# Spring2020V1_5.net
KiCad netlist of a schematic drawn in EAGLE
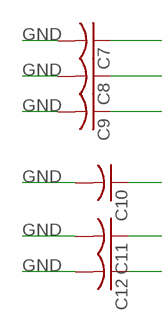
[diagram p0: schematic, sheet 1, part 1 of 2]
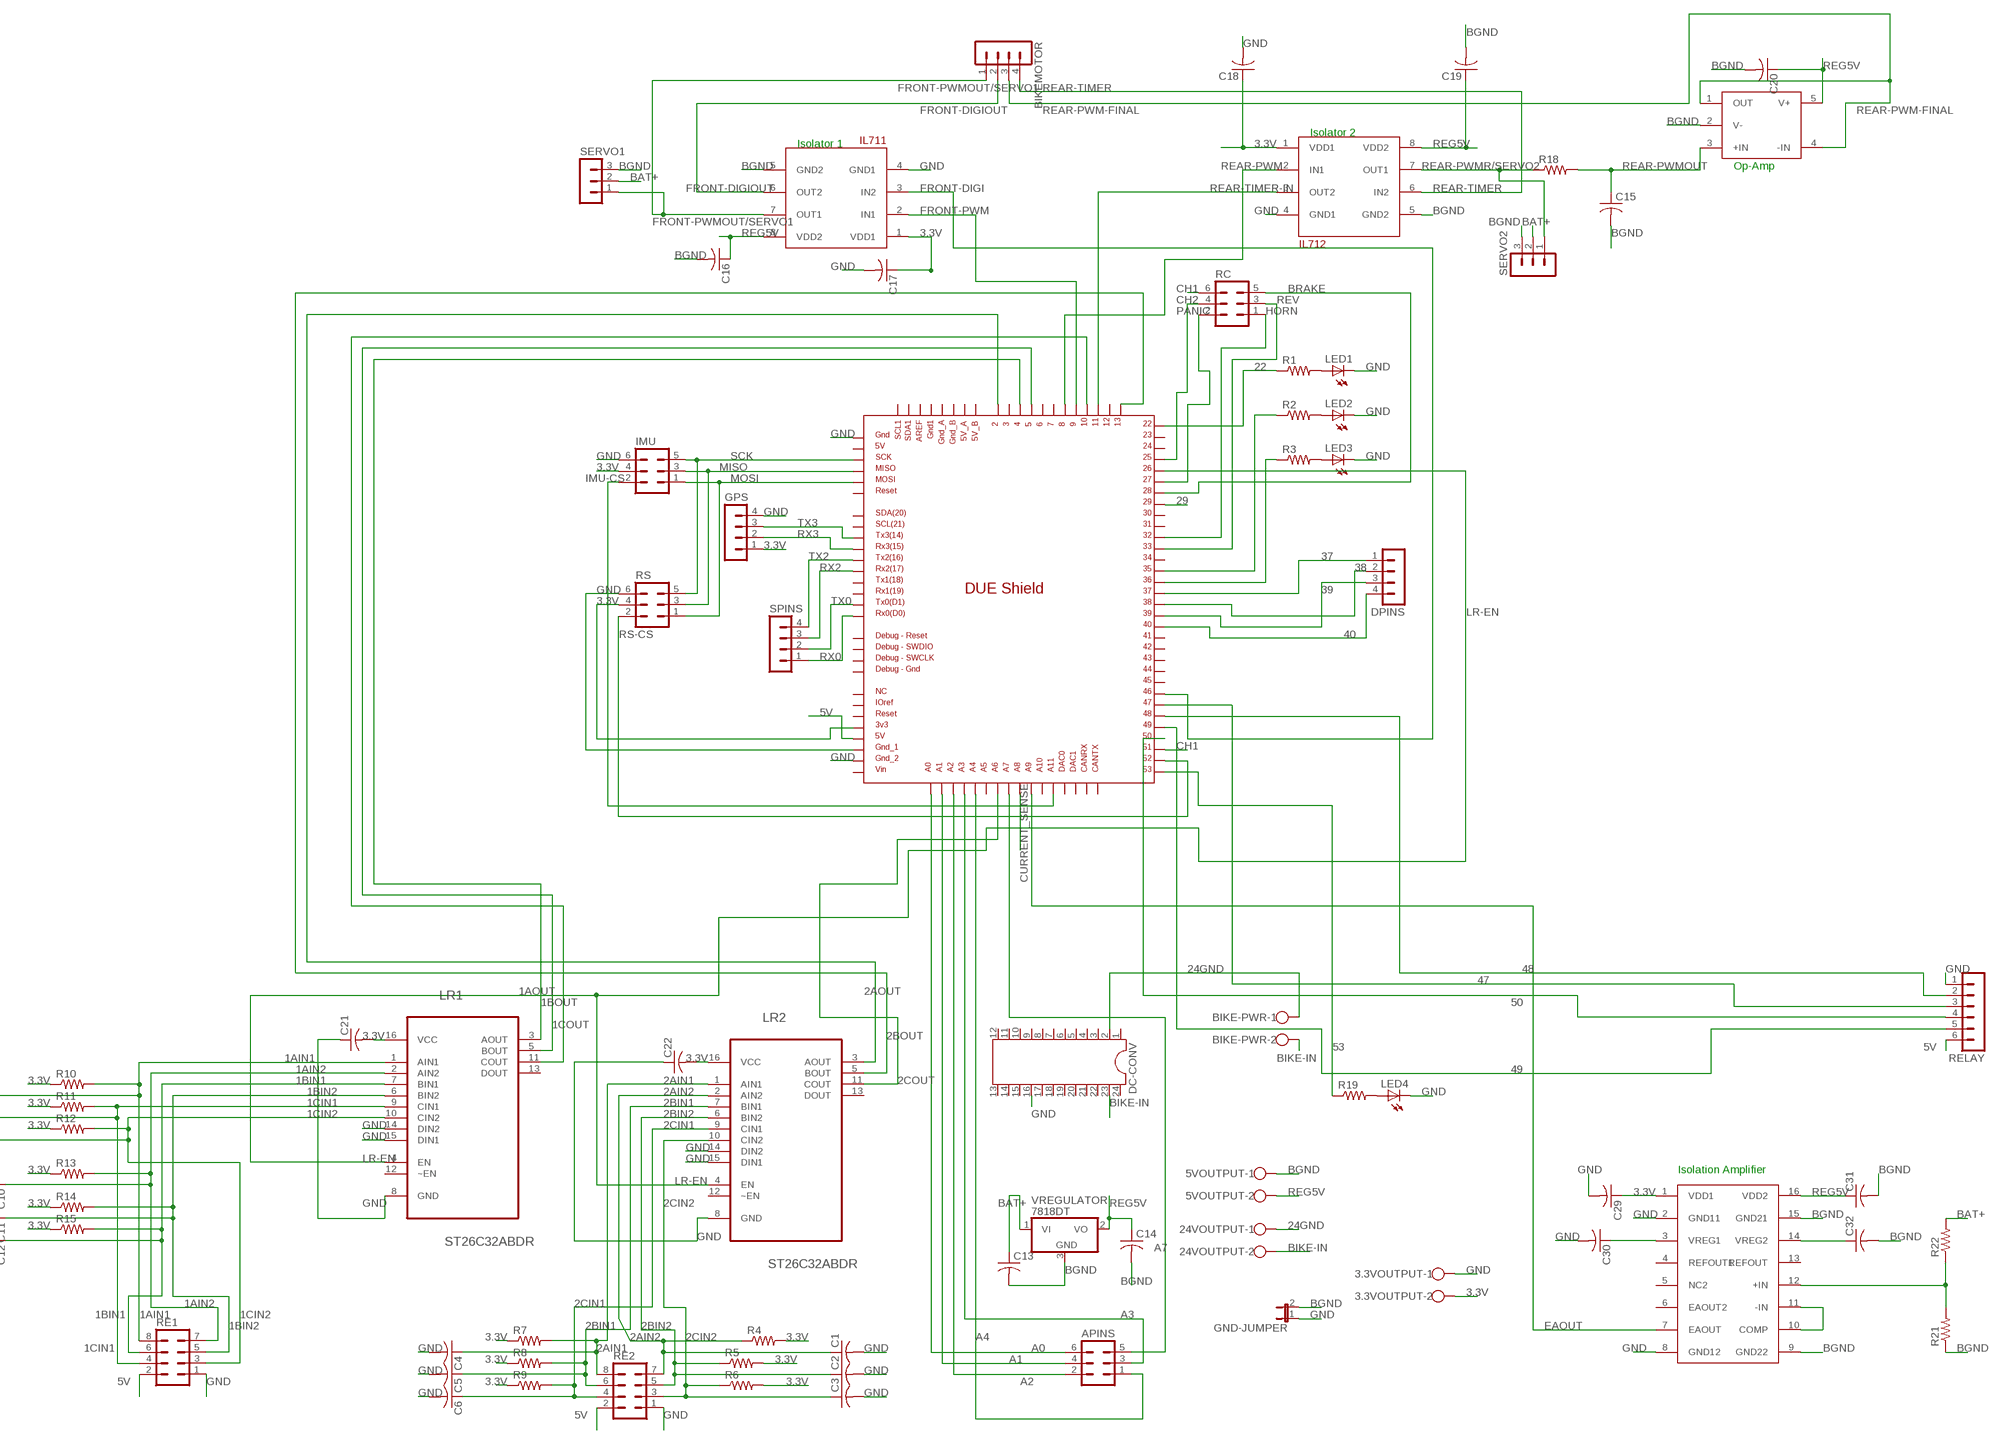
[diagram p1: schematic, sheet 1, part 2 of 2]

(export (version "E")
  (design (tool "Eeschema 10.0.6"))
  (components
    (comp (ref "3.3VOUTPUT")
      (value "W237-102")
      (footprint "eagle-import:W237-102")
      (fields (field (name "MPN") "237-102"))
      (libsource (lib "eagle-import") (part "W237-102"))
    )
    (comp (ref "5VOUTPUT")
      (value "W237-102")
      (footprint "eagle-import:W237-102")
      (fields (field (name "MPN") "237-102"))
      (libsource (lib "eagle-import") (part "W237-102"))
    )
    (comp (ref "24VOUTPUT")
      (value "W237-102")
      (footprint "eagle-import:W237-102")
      (fields (field (name "MPN") "237-102"))
      (libsource (lib "eagle-import") (part "W237-102"))
    )
    (comp (ref "APINS")
      (value "MA03-2")
      (footprint "eagle-import:MA03-2")
      (libsource (lib "eagle-import") (part "MA03-2"))
    )
    (comp (ref "BIKE-PWR")
      (value "W237-102")
      (footprint "eagle-import:W237-102")
      (fields (field (name "MPN") "237-102"))
      (libsource (lib "eagle-import") (part "W237-102"))
    )
    (comp (ref "BIKEMOTOR")
      (value "MA04-1")
      (footprint "eagle-import:MA04-1")
      (libsource (lib "eagle-import") (part "MA04-1"))
    )
    (comp (ref "C1")
      (value "C-US025-025X050")
      (footprint "eagle-import:C025-025X050")
      (libsource (lib "eagle-import") (part "C-US025-025X050"))
    )
    (comp (ref "C2")
      (value "C-US025-025X050")
      (footprint "eagle-import:C025-025X050")
      (libsource (lib "eagle-import") (part "C-US025-025X050"))
    )
    (comp (ref "C3")
      (value "C-US025-025X050")
      (footprint "eagle-import:C025-025X050")
      (libsource (lib "eagle-import") (part "C-US025-025X050"))
    )
    (comp (ref "C4")
      (value "C-US025-025X050")
      (footprint "eagle-import:C025-025X050")
      (libsource (lib "eagle-import") (part "C-US025-025X050"))
    )
    (comp (ref "C5")
      (value "C-US025-025X050")
      (footprint "eagle-import:C025-025X050")
      (libsource (lib "eagle-import") (part "C-US025-025X050"))
    )
    (comp (ref "C6")
      (value "C-US025-025X050")
      (footprint "eagle-import:C025-025X050")
      (libsource (lib "eagle-import") (part "C-US025-025X050"))
    )
    (comp (ref "C7")
      (value "C-US025-025X050")
      (footprint "eagle-import:C025-025X050")
      (libsource (lib "eagle-import") (part "C-US025-025X050"))
    )
    (comp (ref "C8")
      (value "C-US025-025X050")
      (footprint "eagle-import:C025-025X050")
      (libsource (lib "eagle-import") (part "C-US025-025X050"))
    )
    (comp (ref "C9")
      (value "C-US025-025X050")
      (footprint "eagle-import:C025-025X050")
      (libsource (lib "eagle-import") (part "C-US025-025X050"))
    )
    (comp (ref "C10")
      (value "C-US025-025X050")
      (footprint "eagle-import:C025-025X050")
      (libsource (lib "eagle-import") (part "C-US025-025X050"))
    )
    (comp (ref "C11")
      (value "C-US025-025X050")
      (footprint "eagle-import:C025-025X050")
      (libsource (lib "eagle-import") (part "C-US025-025X050"))
    )
    (comp (ref "C12")
      (value "C-US025-025X050")
      (footprint "eagle-import:C025-025X050")
      (libsource (lib "eagle-import") (part "C-US025-025X050"))
    )
    (comp (ref "C13")
      (value "C-US025-050X050")
      (footprint "eagle-import:C025-050X050")
      (libsource (lib "eagle-import") (part "C-US025-050X050"))
    )
    (comp (ref "C14")
      (value "C-US025-050X050")
      (footprint "eagle-import:C025-050X050")
      (libsource (lib "eagle-import") (part "C-US025-050X050"))
    )
    (comp (ref "C15")
      (value "C-US025-050X050")
      (footprint "eagle-import:C025-050X050")
      (libsource (lib "eagle-import") (part "C-US025-050X050"))
    )
    (comp (ref "C16")
      (value "C-US025-050X050")
      (footprint "eagle-import:C025-050X050")
      (libsource (lib "eagle-import") (part "C-US025-050X050"))
    )
    (comp (ref "C17")
      (value "C-US025-050X050")
      (footprint "eagle-import:C025-050X050")
      (libsource (lib "eagle-import") (part "C-US025-050X050"))
    )
    (comp (ref "C18")
      (value "C-US025-050X050")
      (footprint "eagle-import:C025-050X050")
      (libsource (lib "eagle-import") (part "C-US025-050X050"))
    )
    (comp (ref "C19")
      (value "C-US025-050X050")
      (footprint "eagle-import:C025-050X050")
      (libsource (lib "eagle-import") (part "C-US025-050X050"))
    )
    (comp (ref "C20")
      (value "C-US025-050X050")
      (footprint "eagle-import:C025-050X050")
      (libsource (lib "eagle-import") (part "C-US025-050X050"))
    )
    (comp (ref "C21")
      (value "C-US025-050X050")
      (footprint "eagle-import:C025-050X050")
      (libsource (lib "eagle-import") (part "C-US025-050X050"))
    )
    (comp (ref "C22")
      (value "C-US025-050X050")
      (footprint "eagle-import:C025-050X050")
      (libsource (lib "eagle-import") (part "C-US025-050X050"))
    )
    (comp (ref "C29")
      (value "C-US025-050X050")
      (footprint "eagle-import:C025-050X050")
      (libsource (lib "eagle-import") (part "C-US025-050X050"))
    )
    (comp (ref "C30")
      (value "C-US025-050X050")
      (footprint "eagle-import:C025-050X050")
      (libsource (lib "eagle-import") (part "C-US025-050X050"))
    )
    (comp (ref "C31")
      (value "C-US025-050X050")
      (footprint "eagle-import:C025-050X050")
      (libsource (lib "eagle-import") (part "C-US025-050X050"))
    )
    (comp (ref "C32")
      (value "C-US025-050X050")
      (footprint "eagle-import:C025-050X050")
      (libsource (lib "eagle-import") (part "C-US025-050X050"))
    )
    (comp (ref "DC-CONV")
      (value "CU.INC---VAWQ6-Q48-S12H-6")
      (footprint "eagle-import:DIL24-6")
      (libsource (lib "eagle-import") (part "CU.INC---VAWQ6-Q48-S12H-6"))
    )
    (comp (ref "DPINS")
      (value "MA04-1")
      (footprint "eagle-import:MA04-1")
      (libsource (lib "eagle-import") (part "MA04-1"))
    )
    (comp (ref "GND-JUMPER")
      (value "JP1E")
      (footprint "eagle-import:JP1")
      (libsource (lib "eagle-import") (part "JP1E"))
    )
    (comp (ref "GPS")
      (value "MA04-1")
      (footprint "eagle-import:MA04-1")
      (libsource (lib "eagle-import") (part "MA04-1"))
    )
    (comp (ref "IMU")
      (value "MA03-2")
      (footprint "eagle-import:MA03-2")
      (libsource (lib "eagle-import") (part "MA03-2"))
    )
    (comp (ref "LED1")
      (value "LED5MM")
      (footprint "eagle-import:LED5MM")
      (libsource (lib "eagle-import") (part "LED5MM"))
    )
    (comp (ref "LED2")
      (value "LED5MM")
      (footprint "eagle-import:LED5MM")
      (libsource (lib "eagle-import") (part "LED5MM"))
    )
    (comp (ref "LED3")
      (value "LED5MM")
      (footprint "eagle-import:LED5MM")
      (libsource (lib "eagle-import") (part "LED5MM"))
    )
    (comp (ref "LED4")
      (value "LED5MM")
      (footprint "eagle-import:LED5MM")
      (libsource (lib "eagle-import") (part "LED5MM"))
    )
    (comp (ref "LR1")
      (value "ST26C32ABDR")
      (footprint "eagle-import:SOIC127P600X175-16N")
      (libsource (lib "eagle-import") (part "ST26C32ABDR"))
    )
    (comp (ref "LR2")
      (value "ST26C32ABDR")
      (footprint "eagle-import:SOIC127P600X175-16N")
      (libsource (lib "eagle-import") (part "ST26C32ABDR"))
    )
    (comp (ref "OP-AMP")
      (value "OPAMP")
      (footprint "eagle-import:SOT95P280X145-5N")
      (libsource (lib "eagle-import") (part "OPAMP"))
    )
    (comp (ref "R1")
      (value "R-US_0309/10")
      (footprint "eagle-import:0309_10")
      (libsource (lib "eagle-import") (part "R-US_0309/10"))
    )
    (comp (ref "R2")
      (value "R-US_0309/10")
      (footprint "eagle-import:0309_10")
      (libsource (lib "eagle-import") (part "R-US_0309/10"))
    )
    (comp (ref "R3")
      (value "R-US_0309/10")
      (footprint "eagle-import:0309_10")
      (libsource (lib "eagle-import") (part "R-US_0309/10"))
    )
    (comp (ref "R4")
      (value "R-US_0613/15")
      (footprint "eagle-import:P0613_15")
      (libsource (lib "eagle-import") (part "resistor_R-US_0613/15"))
    )
    (comp (ref "R5")
      (value "R-US_0613/15")
      (footprint "eagle-import:P0613_15")
      (libsource (lib "eagle-import") (part "resistor_R-US_0613/15"))
    )
    (comp (ref "R6")
      (value "R-US_0613/15")
      (footprint "eagle-import:P0613_15")
      (libsource (lib "eagle-import") (part "resistor_R-US_0613/15"))
    )
    (comp (ref "R7")
      (value "R-US_0613/15")
      (footprint "eagle-import:P0613_15")
      (libsource (lib "eagle-import") (part "resistor_R-US_0613/15"))
    )
    (comp (ref "R8")
      (value "R-US_0613/15")
      (footprint "eagle-import:P0613_15")
      (libsource (lib "eagle-import") (part "resistor_R-US_0613/15"))
    )
    (comp (ref "R9")
      (value "R-US_0613/15")
      (footprint "eagle-import:P0613_15")
      (libsource (lib "eagle-import") (part "resistor_R-US_0613/15"))
    )
    (comp (ref "R10")
      (value "R-US_0613/15")
      (footprint "eagle-import:P0613_15")
      (libsource (lib "eagle-import") (part "resistor_R-US_0613/15"))
    )
    (comp (ref "R11")
      (value "R-US_0613/15")
      (footprint "eagle-import:P0613_15")
      (libsource (lib "eagle-import") (part "resistor_R-US_0613/15"))
    )
    (comp (ref "R12")
      (value "R-US_0613/15")
      (footprint "eagle-import:P0613_15")
      (libsource (lib "eagle-import") (part "resistor_R-US_0613/15"))
    )
    (comp (ref "R13")
      (value "R-US_0613/15")
      (footprint "eagle-import:P0613_15")
      (libsource (lib "eagle-import") (part "resistor_R-US_0613/15"))
    )
    (comp (ref "R14")
      (value "R-US_0613/15")
      (footprint "eagle-import:P0613_15")
      (libsource (lib "eagle-import") (part "resistor_R-US_0613/15"))
    )
    (comp (ref "R15")
      (value "R-US_0613/15")
      (footprint "eagle-import:P0613_15")
      (libsource (lib "eagle-import") (part "resistor_R-US_0613/15"))
    )
    (comp (ref "R18")
      (value "R-US_0414/15")
      (footprint "eagle-import:0414_15")
      (libsource (lib "eagle-import") (part "resistor_R-US_0414/15"))
    )
    (comp (ref "R19")
      (value "R-US_0309/10")
      (footprint "eagle-import:0309_10")
      (libsource (lib "eagle-import") (part "R-US_0309/10"))
    )
    (comp (ref "R21")
      (value "R-US_0414/15")
      (footprint "eagle-import:0414_15")
      (libsource (lib "eagle-import") (part "resistor_R-US_0414/15"))
    )
    (comp (ref "R22")
      (value "R-US_0414/15")
      (footprint "eagle-import:0414_15")
      (libsource (lib "eagle-import") (part "resistor_R-US_0414/15"))
    )
    (comp (ref "RC")
      (value "MA03-2")
      (footprint "eagle-import:MA03-2")
      (libsource (lib "eagle-import") (part "MA03-2"))
    )
    (comp (ref "RE1")
      (value "MA04-2")
      (footprint "eagle-import:MA04-2")
      (libsource (lib "eagle-import") (part "MA04-2"))
    )
    (comp (ref "RE2")
      (value "MA04-2")
      (footprint "eagle-import:MA04-2")
      (libsource (lib "eagle-import") (part "MA04-2"))
    )
    (comp (ref "RELAY")
      (value "MA06-1")
      (footprint "eagle-import:MA06-1")
      (libsource (lib "eagle-import") (part "MA06-1"))
    )
    (comp (ref "RS")
      (value "MA03-2")
      (footprint "eagle-import:MA03-2")
      (libsource (lib "eagle-import") (part "MA03-2"))
    )
    (comp (ref "SERVO1")
      (value "MA03-1")
      (footprint "eagle-import:MA03-1")
      (libsource (lib "eagle-import") (part "MA03-1"))
    )
    (comp (ref "SERVO2")
      (value "MA03-1")
      (footprint "eagle-import:MA03-1")
      (libsource (lib "eagle-import") (part "MA03-1"))
    )
    (comp (ref "SPINS")
      (value "MA04-1")
      (footprint "eagle-import:MA04-1")
      (libsource (lib "eagle-import") (part "MA04-1"))
    )
    (comp (ref "U$1")
      (value "DUE(NORMAL)")
      (footprint "eagle-import:DUE(NORMAL)")
      (libsource (lib "eagle-import") (part "DUE(NORMAL)"))
    )
    (comp (ref "U$2")
      (value "IL-711")
      (footprint "eagle-import:8PINSOIC")
      (libsource (lib "eagle-import") (part "IL-711"))
    )
    (comp (ref "U$5")
      (value "ISOLATED_ERROR_AMP_ADUM3190")
      (footprint "eagle-import:QSOP16")
      (libsource (lib "eagle-import") (part "ISOLATED_ERROR_AMP_ADUM3190"))
    )
    (comp (ref "U$7")
      (value "IL-712")
      (footprint "eagle-import:8PINSOIC")
      (libsource (lib "eagle-import") (part "IL-712"))
    )
    (comp (ref "VREGULATOR")
      (value "7818DT")
      (footprint "eagle-import:TO252")
      (libsource (lib "eagle-import") (part "78DT18"))
    )
  )
  (nets
    (net (code "1") (name "/1AIN1") (class "Default")
      (node (ref "C7") (pin "1") (pinfunction "1_1") (pintype "passive"))
      (node (ref "LR1") (pin "1") (pinfunction "AIN1_1") (pintype "input"))
      (node (ref "R10") (pin "2") (pinfunction "2_2") (pintype "passive"))
      (node (ref "RE1") (pin "8") (pinfunction "8_8") (pintype "passive"))
    )
    (net (code "2") (name "/1AIN2") (class "Default")
      (node (ref "C10") (pin "1") (pinfunction "1_1") (pintype "passive"))
      (node (ref "LR1") (pin "2") (pinfunction "AIN2_2") (pintype "input"))
      (node (ref "R13") (pin "2") (pinfunction "2_2") (pintype "passive"))
      (node (ref "RE1") (pin "7") (pinfunction "7_7") (pintype "passive"))
    )
    (net (code "3") (name "/1AOUT") (class "Default")
      (node (ref "LR1") (pin "3") (pinfunction "AOUT_3") (pintype "output"))
      (node (ref "U$1") (pin "4") (pinfunction "4_4") (pintype "bidirectional"))
    )
    (net (code "4") (name "/1BIN1") (class "Default")
      (node (ref "C12") (pin "1") (pinfunction "1_1") (pintype "passive"))
      (node (ref "LR1") (pin "7") (pinfunction "BIN1_7") (pintype "input"))
      (node (ref "R15") (pin "2") (pinfunction "2_2") (pintype "passive"))
      (node (ref "RE1") (pin "6") (pinfunction "6_6") (pintype "passive"))
    )
    (net (code "5") (name "/1BIN2") (class "Default")
      (node (ref "C11") (pin "1") (pinfunction "1_1") (pintype "passive"))
      (node (ref "LR1") (pin "6") (pinfunction "BIN2_6") (pintype "input"))
      (node (ref "R14") (pin "2") (pinfunction "2_2") (pintype "passive"))
      (node (ref "RE1") (pin "5") (pinfunction "5_5") (pintype "passive"))
    )
    (net (code "6") (name "/1BOUT") (class "Default")
      (node (ref "LR1") (pin "5") (pinfunction "BOUT_5") (pintype "output"))
      (node (ref "U$1") (pin "5") (pinfunction "5_5") (pintype "bidirectional"))
    )
    (net (code "7") (name "/1CIN1") (class "Default")
      (node (ref "C8") (pin "1") (pinfunction "1_1") (pintype "passive"))
      (node (ref "LR1") (pin "9") (pinfunction "CIN1_9") (pintype "input"))
      (node (ref "R11") (pin "2") (pinfunction "2_2") (pintype "passive"))
      (node (ref "RE1") (pin "4") (pinfunction "4_4") (pintype "passive"))
    )
    (net (code "8") (name "/1CIN2") (class "Default")
      (node (ref "C9") (pin "1") (pinfunction "1_1") (pintype "passive"))
      (node (ref "LR1") (pin "10") (pinfunction "CIN2_10") (pintype "input"))
      (node (ref "R12") (pin "2") (pinfunction "2_2") (pintype "passive"))
      (node (ref "RE1") (pin "3") (pinfunction "3_3") (pintype "passive"))
    )
    (net (code "9") (name "/1COUT") (class "Default")
      (node (ref "LR1") (pin "11") (pinfunction "COUT_11") (pintype "output"))
      (node (ref "U$1") (pin "10") (pinfunction "10_10") (pintype "bidirectional"))
    )
    (net (code "10") (name "/2AIN1") (class "Default")
      (node (ref "C4") (pin "1") (pinfunction "1_1") (pintype "passive"))
      (node (ref "LR2") (pin "1") (pinfunction "AIN1_1") (pintype "input"))
      (node (ref "R7") (pin "2") (pinfunction "2_2") (pintype "passive"))
      (node (ref "RE2") (pin "8") (pinfunction "8_8") (pintype "passive"))
    )
    (net (code "11") (name "/2AIN2") (class "Default")
      (node (ref "C1") (pin "1") (pinfunction "1_1") (pintype "passive"))
      (node (ref "LR2") (pin "2") (pinfunction "AIN2_2") (pintype "input"))
      (node (ref "R4") (pin "1") (pinfunction "1_1") (pintype "passive"))
      (node (ref "RE2") (pin "7") (pinfunction "7_7") (pintype "passive"))
    )
    (net (code "12") (name "/2AOUT") (class "Default")
      (node (ref "LR2") (pin "3") (pinfunction "AOUT_3") (pintype "output"))
      (node (ref "U$1") (pin "2") (pinfunction "2_2") (pintype "bidirectional"))
    )
    (net (code "13") (name "/2BIN1") (class "Default")
      (node (ref "C5") (pin "1") (pinfunction "1_1") (pintype "passive"))
      (node (ref "LR2") (pin "7") (pinfunction "BIN1_7") (pintype "input"))
      (node (ref "R8") (pin "2") (pinfunction "2_2") (pintype "passive"))
      (node (ref "RE2") (pin "6") (pinfunction "6_6") (pintype "passive"))
    )
    (net (code "14") (name "/2BIN2") (class "Default")
      (node (ref "C2") (pin "1") (pinfunction "1_1") (pintype "passive"))
      (node (ref "LR2") (pin "6") (pinfunction "BIN2_6") (pintype "input"))
      (node (ref "R5") (pin "1") (pinfunction "1_1") (pintype "passive"))
      (node (ref "RE2") (pin "5") (pinfunction "5_5") (pintype "passive"))
    )
    (net (code "15") (name "/2BOUT") (class "Default")
      (node (ref "LR2") (pin "5") (pinfunction "BOUT_5") (pintype "output"))
      (node (ref "U$1") (pin "13") (pinfunction "13_13") (pintype "bidirectional"))
    )
    (net (code "16") (name "/2CIN1") (class "Default")
      (node (ref "C6") (pin "1") (pinfunction "1_1") (pintype "passive"))
      (node (ref "LR2") (pin "9") (pinfunction "CIN1_9") (pintype "input"))
      (node (ref "R9") (pin "2") (pinfunction "2_2") (pintype "passive"))
      (node (ref "RE2") (pin "4") (pinfunction "4_4") (pintype "passive"))
    )
    (net (code "17") (name "/2CIN2") (class "Default")
      (node (ref "C3") (pin "1") (pinfunction "1_1") (pintype "passive"))
      (node (ref "LR2") (pin "10") (pinfunction "CIN2_10") (pintype "input"))
      (node (ref "R6") (pin "1") (pinfunction "1_1") (pintype "passive"))
      (node (ref "RE2") (pin "3") (pinfunction "3_3") (pintype "passive"))
    )
    (net (code "18") (name "/2COUT") (class "Default")
      (node (ref "LR2") (pin "11") (pinfunction "COUT_11") (pintype "output"))
      (node (ref "U$1") (pin "A6") (pinfunction "A6_A6") (pintype "bidirectional"))
    )
    (net (code "19") (name "/3.3V") (class "Default")
      (node (ref "3.3VOUTPUT") (pin "2") (pinfunction "KL_2") (pintype "passive"))
      (node (ref "C17") (pin "1") (pinfunction "1_1") (pintype "passive"))
      (node (ref "C18") (pin "1") (pinfunction "1_1") (pintype "passive"))
      (node (ref "C21") (pin "2") (pinfunction "2_2") (pintype "passive"))
      (node (ref "C22") (pin "2") (pinfunction "2_2") (pintype "passive"))
      (node (ref "C29") (pin "1") (pinfunction "1_1") (pintype "passive"))
      (node (ref "GPS") (pin "1") (pinfunction "1_1") (pintype "passive"))
      (node (ref "IMU") (pin "4") (pinfunction "4_4") (pintype "passive"))
      (node (ref "LR1") (pin "16") (pinfunction "VCC_16") (pintype "power_in"))
      (node (ref "LR2") (pin "16") (pinfunction "VCC_16") (pintype "power_in"))
      (node (ref "R10") (pin "1") (pinfunction "1_1") (pintype "passive"))
      (node (ref "R11") (pin "1") (pinfunction "1_1") (pintype "passive"))
      (node (ref "R12") (pin "1") (pinfunction "1_1") (pintype "passive"))
      (node (ref "R13") (pin "1") (pinfunction "1_1") (pintype "passive"))
      (node (ref "R14") (pin "1") (pinfunction "1_1") (pintype "passive"))
      (node (ref "R15") (pin "1") (pinfunction "1_1") (pintype "passive"))
      (node (ref "R4") (pin "2") (pinfunction "2_2") (pintype "passive"))
      (node (ref "R5") (pin "2") (pinfunction "2_2") (pintype "passive"))
      (node (ref "R6") (pin "2") (pinfunction "2_2") (pintype "passive"))
      (node (ref "R7") (pin "1") (pinfunction "1_1") (pintype "passive"))
      (node (ref "R8") (pin "1") (pinfunction "1_1") (pintype "passive"))
      (node (ref "R9") (pin "1") (pinfunction "1_1") (pintype "passive"))
      (node (ref "RS") (pin "4") (pinfunction "4_4") (pintype "passive"))
      (node (ref "U$1") (pin "3V3") (pinfunction "3V3_3V3") (pintype "bidirectional"))
      (node (ref "U$2") (pin "1") (pinfunction "VDD1_1") (pintype "power_in"))
      (node (ref "U$5") (pin "1") (pinfunction "VDD1_1") (pintype "bidirectional"))
      (node (ref "U$7") (pin "1") (pinfunction "VDD1_1") (pintype "power_in"))
    )
    (net (code "20") (name "/5V") (class "Default")
      (node (ref "RE1") (pin "2") (pinfunction "2_2") (pintype "passive"))
      (node (ref "RE2") (pin "2") (pinfunction "2_2") (pintype "passive"))
      (node (ref "RELAY") (pin "6") (pinfunction "6_6") (pintype "passive"))
      (node (ref "U$1") (pin "5V") (pinfunction "5V_5V") (pintype "bidirectional"))
    )
    (net (code "21") (name "/22") (class "Default")
      (node (ref "R1") (pin "1") (pinfunction "1_1") (pintype "passive"))
      (node (ref "U$1") (pin "22") (pinfunction "22_22") (pintype "bidirectional"))
    )
    (net (code "22") (name "/24GND") (class "Default")
      (node (ref "24VOUTPUT") (pin "1") (pinfunction "KL_1") (pintype "passive"))
      (node (ref "BIKE-PWR") (pin "1") (pinfunction "KL_1") (pintype "passive"))
      (node (ref "DC-CONV") (pin "2") (pinfunction "2_2") (pintype "passive"))
    )
    (net (code "23") (name "/29") (class "Default")
      (node (ref "U$1") (pin "29") (pinfunction "29_29") (pintype "bidirectional"))
    )
    (net (code "24") (name "/37") (class "Default")
      (node (ref "DPINS") (pin "1") (pinfunction "1_1") (pintype "passive"))
      (node (ref "U$1") (pin "37") (pinfunction "37_37") (pintype "bidirectional"))
    )
    (net (code "25") (name "/38") (class "Default")
      (node (ref "DPINS") (pin "2") (pinfunction "2_2") (pintype "passive"))
      (node (ref "U$1") (pin "38") (pinfunction "38_38") (pintype "bidirectional"))
    )
    (net (code "26") (name "/39") (class "Default")
      (node (ref "DPINS") (pin "3") (pinfunction "3_3") (pintype "passive"))
      (node (ref "U$1") (pin "39") (pinfunction "39_39") (pintype "bidirectional"))
    )
    (net (code "27") (name "/40") (class "Default")
      (node (ref "DPINS") (pin "4") (pinfunction "4_4") (pintype "passive"))
      (node (ref "U$1") (pin "40") (pinfunction "40_40") (pintype "bidirectional"))
    )
    (net (code "28") (name "/47") (class "Default")
      (node (ref "RELAY") (pin "3") (pinfunction "3_3") (pintype "passive"))
      (node (ref "U$1") (pin "47") (pinfunction "47_47") (pintype "bidirectional"))
    )
    (net (code "29") (name "/48") (class "Default")
      (node (ref "RELAY") (pin "2") (pinfunction "2_2") (pintype "passive"))
      (node (ref "U$1") (pin "48") (pinfunction "48_48") (pintype "bidirectional"))
    )
    (net (code "30") (name "/49") (class "Default")
      (node (ref "RELAY") (pin "5") (pinfunction "5_5") (pintype "passive"))
      (node (ref "U$1") (pin "49") (pinfunction "49_49") (pintype "bidirectional"))
    )
    (net (code "31") (name "/50") (class "Default")
      (node (ref "RELAY") (pin "4") (pinfunction "4_4") (pintype "passive"))
      (node (ref "U$1") (pin "50") (pinfunction "50_50") (pintype "bidirectional"))
    )
    (net (code "32") (name "/53") (class "Default")
      (node (ref "R19") (pin "1") (pinfunction "1_1") (pintype "passive"))
      (node (ref "U$1") (pin "53") (pinfunction "53_53") (pintype "bidirectional"))
    )
    (net (code "33") (name "/A0") (class "Default")
      (node (ref "APINS") (pin "6") (pinfunction "6_6") (pintype "passive"))
      (node (ref "U$1") (pin "A0") (pinfunction "A0_A0") (pintype "bidirectional"))
    )
    (net (code "34") (name "/A1") (class "Default")
      (node (ref "APINS") (pin "4") (pinfunction "4_4") (pintype "passive"))
      (node (ref "U$1") (pin "A1") (pinfunction "A1_A1") (pintype "bidirectional"))
    )
    (net (code "35") (name "/A2") (class "Default")
      (node (ref "APINS") (pin "2") (pinfunction "2_2") (pintype "passive"))
      (node (ref "U$1") (pin "A2") (pinfunction "A2_A2") (pintype "bidirectional"))
    )
    (net (code "36") (name "/A3") (class "Default")
      (node (ref "APINS") (pin "3") (pinfunction "3_3") (pintype "passive"))
      (node (ref "U$1") (pin "A3") (pinfunction "A3_A3") (pintype "bidirectional"))
    )
    (net (code "37") (name "/A4") (class "Default")
      (node (ref "APINS") (pin "1") (pinfunction "1_1") (pintype "passive"))
      (node (ref "U$1") (pin "A4") (pinfunction "A4_A4") (pintype "bidirectional"))
    )
    (net (code "38") (name "/A7") (class "Default")
      (node (ref "APINS") (pin "5") (pinfunction "5_5") (pintype "passive"))
      (node (ref "U$1") (pin "A7") (pinfunction "A7_A7") (pintype "bidirectional"))
    )
    (net (code "39") (name "/BAT+") (class "Default")
      (node (ref "C13") (pin "1") (pinfunction "1_1") (pintype "passive"))
      (node (ref "R22") (pin "2") (pinfunction "2_2") (pintype "passive"))
      (node (ref "SERVO1") (pin "2") (pinfunction "2_2") (pintype "passive"))
      (node (ref "SERVO2") (pin "2") (pinfunction "2_2") (pintype "passive"))
      (node (ref "VREGULATOR") (pin "1") (pinfunction "VI_1") (pintype "input"))
    )
    (net (code "40") (name "/BGND") (class "Default")
      (node (ref "5VOUTPUT") (pin "1") (pinfunction "KL_1") (pintype "passive"))
      (node (ref "C13") (pin "2") (pinfunction "2_2") (pintype "passive"))
      (node (ref "C14") (pin "2") (pinfunction "2_2") (pintype "passive"))
      (node (ref "C15") (pin "2") (pinfunction "2_2") (pintype "passive"))
      (node (ref "C16") (pin "2") (pinfunction "2_2") (pintype "passive"))
      (node (ref "C19") (pin "2") (pinfunction "2_2") (pintype "passive"))
      (node (ref "C20") (pin "2") (pinfunction "2_2") (pintype "passive"))
      (node (ref "C31") (pin "2") (pinfunction "2_2") (pintype "passive"))
      (node (ref "C32") (pin "2") (pinfunction "2_2") (pintype "passive"))
      (node (ref "GND-JUMPER") (pin "2") (pinfunction "2_2") (pintype "passive"))
      (node (ref "OP-AMP") (pin "2") (pinfunction "V-_2") (pintype "output"))
      (node (ref "R21") (pin "1") (pinfunction "1_1") (pintype "passive"))
      (node (ref "SERVO1") (pin "3") (pinfunction "3_3") (pintype "passive"))
      (node (ref "SERVO2") (pin "3") (pinfunction "3_3") (pintype "passive"))
      (node (ref "U$2") (pin "5") (pinfunction "GND2_5") (pintype "power_in"))
      (node (ref "U$5") (pin "15") (pinfunction "GND21_15") (pintype "bidirectional"))
      (node (ref "U$5") (pin "9") (pinfunction "GND22_9") (pintype "bidirectional"))
      (node (ref "U$7") (pin "5") (pinfunction "GND2_5") (pintype "power_in"))
      (node (ref "VREGULATOR") (pin "3") (pinfunction "GND_3") (pintype "passive"))
    )
    (net (code "41") (name "/BIKE-IN") (class "Default")
      (node (ref "24VOUTPUT") (pin "2") (pinfunction "KL_2") (pintype "passive"))
      (node (ref "BIKE-PWR") (pin "2") (pinfunction "KL_2") (pintype "passive"))
      (node (ref "DC-CONV") (pin "23") (pinfunction "23_23") (pintype "passive"))
    )
    (net (code "42") (name "/BRAKE") (class "Default")
      (node (ref "RC") (pin "5") (pinfunction "5_5") (pintype "passive"))
      (node (ref "U$1") (pin "28") (pinfunction "28_28") (pintype "bidirectional"))
    )
    (net (code "43") (name "/CH1") (class "Default")
      (node (ref "RC") (pin "6") (pinfunction "6_6") (pintype "passive"))
      (node (ref "U$1") (pin "51") (pinfunction "51_51") (pintype "bidirectional"))
    )
    (net (code "44") (name "/CH2") (class "Default")
      (node (ref "RC") (pin "4") (pinfunction "4_4") (pintype "passive"))
      (node (ref "U$1") (pin "25") (pinfunction "25_25") (pintype "bidirectional"))
    )
    (net (code "45") (name "/CURRENT_SENSE") (class "Default")
      (node (ref "U$1") (pin "A8") (pinfunction "A8_A8") (pintype "bidirectional"))
    )
    (net (code "46") (name "/EAOUT") (class "Default")
      (node (ref "U$1") (pin "A9") (pinfunction "A9_A9") (pintype "bidirectional"))
      (node (ref "U$5") (pin "7") (pinfunction "EAOUT_7") (pintype "bidirectional"))
    )
    (net (code "47") (name "/FRONT-DIGI") (class "Default")
      (node (ref "U$1") (pin "46") (pinfunction "46_46") (pintype "bidirectional"))
      (node (ref "U$2") (pin "3") (pinfunction "IN2_3") (pintype "input"))
    )
    (net (code "48") (name "/FRONT-DIGIOUT") (class "Default")
      (node (ref "BIKEMOTOR") (pin "2") (pinfunction "2_2") (pintype "passive"))
      (node (ref "U$2") (pin "6") (pinfunction "OUT2_6") (pintype "output"))
    )
    (net (code "49") (name "/FRONT-PWM") (class "Default")
      (node (ref "U$1") (pin "9") (pinfunction "9_9") (pintype "bidirectional"))
      (node (ref "U$2") (pin "2") (pinfunction "IN1_2") (pintype "input"))
    )
    (net (code "50") (name "/FRONT-PWMOUT{slash}SERVO1") (class "Default")
      (node (ref "BIKEMOTOR") (pin "1") (pinfunction "1_1") (pintype "passive"))
      (node (ref "SERVO1") (pin "1") (pinfunction "1_1") (pintype "passive"))
      (node (ref "U$2") (pin "7") (pinfunction "OUT1_7") (pintype "output"))
    )
    (net (code "51") (name "/GND") (class "Default")
      (node (ref "3.3VOUTPUT") (pin "1") (pinfunction "KL_1") (pintype "passive"))
      (node (ref "C1") (pin "2") (pinfunction "2_2") (pintype "passive"))
      (node (ref "C10") (pin "2") (pinfunction "2_2") (pintype "passive"))
      (node (ref "C11") (pin "2") (pinfunction "2_2") (pintype "passive"))
      (node (ref "C12") (pin "2") (pinfunction "2_2") (pintype "passive"))
      (node (ref "C17") (pin "2") (pinfunction "2_2") (pintype "passive"))
      (node (ref "C18") (pin "2") (pinfunction "2_2") (pintype "passive"))
      (node (ref "C2") (pin "2") (pinfunction "2_2") (pintype "passive"))
      (node (ref "C21") (pin "1") (pinfunction "1_1") (pintype "passive"))
      (node (ref "C22") (pin "1") (pinfunction "1_1") (pintype "passive"))
      (node (ref "C29") (pin "2") (pinfunction "2_2") (pintype "passive"))
      (node (ref "C3") (pin "2") (pinfunction "2_2") (pintype "passive"))
      (node (ref "C30") (pin "2") (pinfunction "2_2") (pintype "passive"))
      (node (ref "C4") (pin "2") (pinfunction "2_2") (pintype "passive"))
      (node (ref "C5") (pin "2") (pinfunction "2_2") (pintype "passive"))
      (node (ref "C6") (pin "2") (pinfunction "2_2") (pintype "passive"))
      (node (ref "C7") (pin "2") (pinfunction "2_2") (pintype "passive"))
      (node (ref "C8") (pin "2") (pinfunction "2_2") (pintype "passive"))
      (node (ref "C9") (pin "2") (pinfunction "2_2") (pintype "passive"))
      (node (ref "DC-CONV") (pin "16") (pinfunction "16_16") (pintype "passive"))
      (node (ref "GND-JUMPER") (pin "1") (pinfunction "1_1") (pintype "passive"))
      (node (ref "GPS") (pin "4") (pinfunction "4_4") (pintype "passive"))
      (node (ref "IMU") (pin "6") (pinfunction "6_6") (pintype "passive"))
      (node (ref "LED1") (pin "K") (pinfunction "C_K") (pintype "passive"))
      (node (ref "LED2") (pin "K") (pinfunction "C_K") (pintype "passive"))
      (node (ref "LED3") (pin "K") (pinfunction "C_K") (pintype "passive"))
      (node (ref "LED4") (pin "K") (pinfunction "C_K") (pintype "passive"))
      (node (ref "LR1") (pin "14") (pinfunction "DIN2_14") (pintype "input"))
      (node (ref "LR1") (pin "15") (pinfunction "DIN1_15") (pintype "input"))
      (node (ref "LR1") (pin "8") (pinfunction "GND_8") (pintype "passive"))
      (node (ref "LR2") (pin "14") (pinfunction "DIN2_14") (pintype "input"))
      (node (ref "LR2") (pin "15") (pinfunction "DIN1_15") (pintype "input"))
      (node (ref "LR2") (pin "8") (pinfunction "GND_8") (pintype "passive"))
      (node (ref "RE1") (pin "1") (pinfunction "1_1") (pintype "passive"))
      (node (ref "RE2") (pin "1") (pinfunction "1_1") (pintype "passive"))
      (node (ref "RELAY") (pin "1") (pinfunction "1_1") (pintype "passive"))
      (node (ref "RS") (pin "6") (pinfunction "6_6") (pintype "passive"))
      (node (ref "U$1") (pin "5V_ICSP") (pinfunction "5V_ICSP_5V_ICSP") (pintype "bidirectional"))
      (node (ref "U$1") (pin "GND_1") (pinfunction "GND_1_GND_1") (pintype "bidirectional"))
      (node (ref "U$1") (pin "GND_2") (pinfunction "GND_2_GND_2") (pintype "bidirectional"))
      (node (ref "U$2") (pin "4") (pinfunction "GND1_4") (pintype "power_in"))
      (node (ref "U$5") (pin "2") (pinfunction "GND11_2") (pintype "bidirectional"))
      (node (ref "U$5") (pin "8") (pinfunction "GND12_8") (pintype "bidirectional"))
      (node (ref "U$7") (pin "4") (pinfunction "GND1_4") (pintype "power_in"))
    )
    (net (code "52") (name "/HORN") (class "Default")
      (node (ref "RC") (pin "1") (pinfunction "1_1") (pintype "passive"))
      (node (ref "U$1") (pin "32") (pinfunction "32_32") (pintype "bidirectional"))
    )
    (net (code "53") (name "/IMU-CS") (class "Default")
      (node (ref "IMU") (pin "2") (pinfunction "2_2") (pintype "passive"))
      (node (ref "U$1") (pin "A11") (pinfunction "A11_A11") (pintype "bidirectional"))
    )
    (net (code "54") (name "/LR-EN") (class "Default")
      (node (ref "LR1") (pin "4") (pinfunction "EN_4") (pintype "input"))
      (node (ref "LR2") (pin "4") (pinfunction "EN_4") (pintype "input"))
      (node (ref "U$1") (pin "26") (pinfunction "26_26") (pintype "bidirectional"))
    )
    (net (code "55") (name "/MISO") (class "Default")
      (node (ref "IMU") (pin "3") (pinfunction "3_3") (pintype "passive"))
      (node (ref "RS") (pin "3") (pinfunction "3_3") (pintype "passive"))
      (node (ref "U$1") (pin "MISO_ICSP") (pinfunction "MISO_ICSP_MISO_ICSP") (pintype "bidirectional"))
    )
    (net (code "56") (name "/MOSI") (class "Default")
      (node (ref "IMU") (pin "1") (pinfunction "1_1") (pintype "passive"))
      (node (ref "RS") (pin "1") (pinfunction "1_1") (pintype "passive"))
      (node (ref "U$1") (pin "MOSI_ICSP") (pinfunction "MOSI_ICSP_MOSI_ICSP") (pintype "bidirectional"))
    )
    (net (code "57") (name "/PANIC") (class "Default")
      (node (ref "RC") (pin "2") (pinfunction "2_2") (pintype "passive"))
      (node (ref "U$1") (pin "27") (pinfunction "27_27") (pintype "bidirectional"))
    )
    (net (code "58") (name "/REAR-PWM") (class "Default")
      (node (ref "U$1") (pin "8") (pinfunction "8_8") (pintype "bidirectional"))
      (node (ref "U$7") (pin "2") (pinfunction "IN1_2") (pintype "input"))
    )
    (net (code "59") (name "/REAR-PWM-FINAL") (class "Default")
      (node (ref "BIKEMOTOR") (pin "3") (pinfunction "3_3") (pintype "passive"))
      (node (ref "OP-AMP") (pin "1") (pinfunction "OUT_1") (pintype "output"))
      (node (ref "OP-AMP") (pin "4") (pinfunction "-IN_4") (pintype "input"))
    )
    (net (code "60") (name "/REAR-PWMOUT") (class "Default")
      (node (ref "C15") (pin "1") (pinfunction "1_1") (pintype "passive"))
      (node (ref "OP-AMP") (pin "3") (pinfunction "+IN_3") (pintype "input"))
      (node (ref "R18") (pin "2") (pinfunction "2_2") (pintype "passive"))
    )
    (net (code "61") (name "/REAR-PWMR{slash}SERVO2") (class "Default")
      (node (ref "R18") (pin "1") (pinfunction "1_1") (pintype "passive"))
      (node (ref "SERVO2") (pin "1") (pinfunction "1_1") (pintype "passive"))
      (node (ref "U$7") (pin "7") (pinfunction "OUT1_7") (pintype "output"))
    )
    (net (code "62") (name "/REAR-TIMER") (class "Default")
      (node (ref "BIKEMOTOR") (pin "4") (pinfunction "4_4") (pintype "passive"))
      (node (ref "U$7") (pin "6") (pinfunction "IN2_6") (pintype "input"))
    )
    (net (code "63") (name "/REAR-TIMER-IN") (class "Default")
      (node (ref "U$1") (pin "11") (pinfunction "11_11") (pintype "bidirectional"))
      (node (ref "U$7") (pin "3") (pinfunction "OUT2_3") (pintype "output"))
    )
    (net (code "64") (name "/REG5V") (class "Default")
      (node (ref "5VOUTPUT") (pin "2") (pinfunction "KL_2") (pintype "passive"))
      (node (ref "C14") (pin "1") (pinfunction "1_1") (pintype "passive"))
      (node (ref "C16") (pin "1") (pinfunction "1_1") (pintype "passive"))
      (node (ref "C19") (pin "1") (pinfunction "1_1") (pintype "passive"))
      (node (ref "C20") (pin "1") (pinfunction "1_1") (pintype "passive"))
      (node (ref "C31") (pin "1") (pinfunction "1_1") (pintype "passive"))
      (node (ref "OP-AMP") (pin "5") (pinfunction "V+_5") (pintype "power_in"))
      (node (ref "U$2") (pin "8") (pinfunction "VDD2_8") (pintype "power_in"))
      (node (ref "U$5") (pin "16") (pinfunction "VDD2_16") (pintype "bidirectional"))
      (node (ref "U$7") (pin "8") (pinfunction "VDD2_8") (pintype "power_in"))
      (node (ref "VREGULATOR") (pin "2") (pinfunction "VO_2") (pintype "passive"))
    )
    (net (code "65") (name "/REV") (class "Default")
      (node (ref "RC") (pin "3") (pinfunction "3_3") (pintype "passive"))
      (node (ref "U$1") (pin "33") (pinfunction "33_33") (pintype "bidirectional"))
    )
    (net (code "66") (name "/RS-CS") (class "Default")
      (node (ref "RS") (pin "2") (pinfunction "2_2") (pintype "passive"))
      (node (ref "U$1") (pin "52") (pinfunction "52_52") (pintype "bidirectional"))
    )
    (net (code "67") (name "/RX0") (class "Default")
      (node (ref "SPINS") (pin "1") (pinfunction "1_1") (pintype "passive"))
      (node (ref "U$1") (pin "RX0") (pinfunction "RX0_RX0") (pintype "bidirectional"))
    )
    (net (code "68") (name "/RX2") (class "Default")
      (node (ref "SPINS") (pin "3") (pinfunction "3_3") (pintype "passive"))
      (node (ref "U$1") (pin "RX2") (pinfunction "RX2_RX2") (pintype "bidirectional"))
    )
    (net (code "69") (name "/RX3") (class "Default")
      (node (ref "GPS") (pin "2") (pinfunction "2_2") (pintype "passive"))
      (node (ref "U$1") (pin "RX3") (pinfunction "RX3_RX3") (pintype "bidirectional"))
    )
    (net (code "70") (name "/SCK") (class "Default")
      (node (ref "IMU") (pin "5") (pinfunction "5_5") (pintype "passive"))
      (node (ref "RS") (pin "5") (pinfunction "5_5") (pintype "passive"))
      (node (ref "U$1") (pin "SCK_ICSP") (pinfunction "SCK_ICSP_SCK_ICSP") (pintype "bidirectional"))
    )
    (net (code "71") (name "/TX0") (class "Default")
      (node (ref "SPINS") (pin "2") (pinfunction "2_2") (pintype "passive"))
      (node (ref "U$1") (pin "TX0") (pinfunction "TX0_TX0") (pintype "bidirectional"))
    )
    (net (code "72") (name "/TX2") (class "Default")
      (node (ref "SPINS") (pin "4") (pinfunction "4_4") (pintype "passive"))
      (node (ref "U$1") (pin "TX2") (pinfunction "TX2_TX2") (pintype "bidirectional"))
    )
    (net (code "73") (name "/TX3") (class "Default")
      (node (ref "GPS") (pin "3") (pinfunction "3_3") (pintype "passive"))
      (node (ref "U$1") (pin "TX3") (pinfunction "TX3_TX3") (pintype "bidirectional"))
    )
    (net (code "74") (name "Net-(LED1-PadA)") (class "Default")
      (node (ref "LED1") (pin "A") (pinfunction "A_A") (pintype "passive"))
      (node (ref "R1") (pin "2") (pinfunction "2_2") (pintype "passive"))
    )
    (net (code "75") (name "Net-(LED2-PadA)") (class "Default")
      (node (ref "LED2") (pin "A") (pinfunction "A_A") (pintype "passive"))
      (node (ref "R2") (pin "2") (pinfunction "2_2") (pintype "passive"))
    )
    (net (code "76") (name "Net-(LED3-PadA)") (class "Default")
      (node (ref "LED3") (pin "A") (pinfunction "A_A") (pintype "passive"))
      (node (ref "R3") (pin "2") (pinfunction "2_2") (pintype "passive"))
    )
    (net (code "77") (name "Net-(LED4-PadA)") (class "Default")
      (node (ref "LED4") (pin "A") (pinfunction "A_A") (pintype "passive"))
      (node (ref "R19") (pin "2") (pinfunction "2_2") (pintype "passive"))
    )
    (net (code "78") (name "Net-(R2-Pad1)") (class "Default")
      (node (ref "R2") (pin "1") (pinfunction "1_1") (pintype "passive"))
      (node (ref "U$1") (pin "35") (pinfunction "35_35") (pintype "bidirectional"))
    )
    (net (code "79") (name "Net-(R3-Pad1)") (class "Default")
      (node (ref "R3") (pin "1") (pinfunction "1_1") (pintype "passive"))
      (node (ref "U$1") (pin "36") (pinfunction "36_36") (pintype "bidirectional"))
    )
    (net (code "80") (name "Net-(U$5-+IN)") (class "Default")
      (node (ref "R21") (pin "2") (pinfunction "2_2") (pintype "passive"))
      (node (ref "R22") (pin "1") (pinfunction "1_1") (pintype "passive"))
      (node (ref "U$5") (pin "12") (pinfunction "+IN_12") (pintype "bidirectional"))
    )
    (net (code "81") (name "Net-(U$5--IN)") (class "Default")
      (node (ref "U$5") (pin "10") (pinfunction "COMP_10") (pintype "bidirectional"))
      (node (ref "U$5") (pin "11") (pinfunction "-IN_11") (pintype "bidirectional"))
    )
    (net (code "82") (name "Net-(U$5-VREG1)") (class "Default")
      (node (ref "C30") (pin "1") (pinfunction "1_1") (pintype "passive"))
      (node (ref "U$5") (pin "3") (pinfunction "VREG1_3") (pintype "bidirectional"))
    )
    (net (code "83") (name "Net-(U$5-VREG2)") (class "Default")
      (node (ref "C32") (pin "1") (pinfunction "1_1") (pintype "passive"))
      (node (ref "U$5") (pin "14") (pinfunction "VREG2_14") (pintype "bidirectional"))
    )
    (net (code "84") (name "unconnected-(DC-CONV-Pad1)") (class "Default")
      (node (ref "DC-CONV") (pin "1") (pinfunction "1_1") (pintype "passive"))
    )
    (net (code "85") (name "unconnected-(DC-CONV-Pad3)") (class "Default")
      (node (ref "DC-CONV") (pin "3") (pinfunction "3_3") (pintype "passive"))
    )
    (net (code "86") (name "unconnected-(DC-CONV-Pad4)") (class "Default")
      (node (ref "DC-CONV") (pin "4") (pinfunction "4_4") (pintype "passive"))
    )
    (net (code "87") (name "unconnected-(DC-CONV-Pad5)") (class "Default")
      (node (ref "DC-CONV") (pin "5") (pinfunction "5_5") (pintype "passive"))
    )
    (net (code "88") (name "unconnected-(DC-CONV-Pad6)") (class "Default")
      (node (ref "DC-CONV") (pin "6") (pinfunction "6_6") (pintype "passive"))
    )
    (net (code "89") (name "unconnected-(DC-CONV-Pad7)") (class "Default")
      (node (ref "DC-CONV") (pin "7") (pinfunction "7_7") (pintype "passive"))
    )
    (net (code "90") (name "unconnected-(DC-CONV-Pad8)") (class "Default")
      (node (ref "DC-CONV") (pin "8") (pinfunction "8_8") (pintype "passive"))
    )
    (net (code "91") (name "unconnected-(DC-CONV-Pad9)") (class "Default")
      (node (ref "DC-CONV") (pin "9") (pinfunction "9_9") (pintype "passive"))
    )
    (net (code "92") (name "unconnected-(DC-CONV-Pad10)") (class "Default")
      (node (ref "DC-CONV") (pin "10") (pinfunction "10_10") (pintype "passive"))
    )
    (net (code "93") (name "unconnected-(DC-CONV-Pad11)") (class "Default")
      (node (ref "DC-CONV") (pin "11") (pinfunction "11_11") (pintype "passive"))
    )
    (net (code "94") (name "unconnected-(DC-CONV-Pad12)") (class "Default")
      (node (ref "DC-CONV") (pin "12") (pinfunction "12_12") (pintype "passive"))
    )
    (net (code "95") (name "unconnected-(DC-CONV-Pad13)") (class "Default")
      (node (ref "DC-CONV") (pin "13") (pinfunction "13_13") (pintype "passive"))
    )
    (net (code "96") (name "unconnected-(DC-CONV-Pad14)") (class "Default")
      (node (ref "DC-CONV") (pin "14") (pinfunction "14_14") (pintype "passive"))
    )
    (net (code "97") (name "unconnected-(DC-CONV-Pad15)") (class "Default")
      (node (ref "DC-CONV") (pin "15") (pinfunction "15_15") (pintype "passive"))
    )
    (net (code "98") (name "unconnected-(DC-CONV-Pad17)") (class "Default")
      (node (ref "DC-CONV") (pin "17") (pinfunction "17_17") (pintype "passive"))
    )
    (net (code "99") (name "unconnected-(DC-CONV-Pad18)") (class "Default")
      (node (ref "DC-CONV") (pin "18") (pinfunction "18_18") (pintype "passive"))
    )
    (net (code "100") (name "unconnected-(DC-CONV-Pad19)") (class "Default")
      (node (ref "DC-CONV") (pin "19") (pinfunction "19_19") (pintype "passive"))
    )
    (net (code "101") (name "unconnected-(DC-CONV-Pad20)") (class "Default")
      (node (ref "DC-CONV") (pin "20") (pinfunction "20_20") (pintype "passive"))
    )
    (net (code "102") (name "unconnected-(DC-CONV-Pad21)") (class "Default")
      (node (ref "DC-CONV") (pin "21") (pinfunction "21_21") (pintype "passive"))
    )
    (net (code "103") (name "unconnected-(DC-CONV-Pad22)") (class "Default")
      (node (ref "DC-CONV") (pin "22") (pinfunction "22_22") (pintype "passive"))
    )
    (net (code "104") (name "unconnected-(DC-CONV-Pad24)") (class "Default")
      (node (ref "DC-CONV") (pin "24") (pinfunction "24_24") (pintype "passive"))
    )
    (net (code "105") (name "unconnected-(LR1-DOUT-Pad13)") (class "Default")
      (node (ref "LR1") (pin "13") (pinfunction "DOUT_13") (pintype "output"))
    )
    (net (code "106") (name "unconnected-(LR1-~{EN}-Pad12)") (class "Default")
      (node (ref "LR1") (pin "12") (pinfunction "~{EN}_12") (pintype "input"))
    )
    (net (code "107") (name "unconnected-(LR2-DOUT-Pad13)") (class "Default")
      (node (ref "LR2") (pin "13") (pinfunction "DOUT_13") (pintype "output"))
    )
    (net (code "108") (name "unconnected-(LR2-~{EN}-Pad12)") (class "Default")
      (node (ref "LR2") (pin "12") (pinfunction "~{EN}_12") (pintype "input"))
    )
    (net (code "109") (name "unconnected-(U$1-Pad3)") (class "Default")
      (node (ref "U$1") (pin "3") (pinfunction "3_3") (pintype "bidirectional"))
    )
    (net (code "110") (name "unconnected-(U$1-Pad5V_A)") (class "Default")
      (node (ref "U$1") (pin "5V_A") (pinfunction "5V_A_5V_A") (pintype "bidirectional"))
    )
    (net (code "111") (name "unconnected-(U$1-Pad5V_B)") (class "Default")
      (node (ref "U$1") (pin "5V_B") (pinfunction "5V_B_5V_B") (pintype "bidirectional"))
    )
    (net (code "112") (name "unconnected-(U$1-Pad6)") (class "Default")
      (node (ref "U$1") (pin "6") (pinfunction "6_6") (pintype "bidirectional"))
    )
    (net (code "113") (name "unconnected-(U$1-Pad7)") (class "Default")
      (node (ref "U$1") (pin "7") (pinfunction "7_7") (pintype "bidirectional"))
    )
    (net (code "114") (name "unconnected-(U$1-Pad12)") (class "Default")
      (node (ref "U$1") (pin "12") (pinfunction "12_12") (pintype "bidirectional"))
    )
    (net (code "115") (name "unconnected-(U$1-Pad23)") (class "Default")
      (node (ref "U$1") (pin "23") (pinfunction "23_23") (pintype "bidirectional"))
    )
    (net (code "116") (name "unconnected-(U$1-Pad24)") (class "Default")
      (node (ref "U$1") (pin "24") (pinfunction "24_24") (pintype "bidirectional"))
    )
    (net (code "117") (name "unconnected-(U$1-Pad30)") (class "Default")
      (node (ref "U$1") (pin "30") (pinfunction "30_30") (pintype "bidirectional"))
    )
    (net (code "118") (name "unconnected-(U$1-Pad31)") (class "Default")
      (node (ref "U$1") (pin "31") (pinfunction "31_31") (pintype "bidirectional"))
    )
    (net (code "119") (name "unconnected-(U$1-Pad34)") (class "Default")
      (node (ref "U$1") (pin "34") (pinfunction "34_34") (pintype "bidirectional"))
    )
    (net (code "120") (name "unconnected-(U$1-Pad41)") (class "Default")
      (node (ref "U$1") (pin "41") (pinfunction "41_41") (pintype "bidirectional"))
    )
    (net (code "121") (name "unconnected-(U$1-Pad42)") (class "Default")
      (node (ref "U$1") (pin "42") (pinfunction "42_42") (pintype "bidirectional"))
    )
    (net (code "122") (name "unconnected-(U$1-Pad43)") (class "Default")
      (node (ref "U$1") (pin "43") (pinfunction "43_43") (pintype "bidirectional"))
    )
    (net (code "123") (name "unconnected-(U$1-Pad44)") (class "Default")
      (node (ref "U$1") (pin "44") (pinfunction "44_44") (pintype "bidirectional"))
    )
    (net (code "124") (name "unconnected-(U$1-Pad45)") (class "Default")
      (node (ref "U$1") (pin "45") (pinfunction "45_45") (pintype "bidirectional"))
    )
    (net (code "125") (name "unconnected-(U$1-PadA5)") (class "Default")
      (node (ref "U$1") (pin "A5") (pinfunction "A5_A5") (pintype "bidirectional"))
    )
    (net (code "126") (name "unconnected-(U$1-PadA10)") (class "Default")
      (node (ref "U$1") (pin "A10") (pinfunction "A10_A10") (pintype "bidirectional"))
    )
    (net (code "127") (name "unconnected-(U$1-PadAREF)") (class "Default")
      (node (ref "U$1") (pin "AREF") (pinfunction "AREF_AREF") (pintype "bidirectional"))
    )
    (net (code "128") (name "unconnected-(U$1-PadCANRX)") (class "Default")
      (node (ref "U$1") (pin "CANRX") (pinfunction "CANRX_CANRX") (pintype "bidirectional"))
    )
    (net (code "129") (name "unconnected-(U$1-PadCANTX)") (class "Default")
      (node (ref "U$1") (pin "CANTX") (pinfunction "CANTX_CANTX") (pintype "bidirectional"))
    )
    (net (code "130") (name "unconnected-(U$1-PadDAC0)") (class "Default")
      (node (ref "U$1") (pin "DAC0") (pinfunction "DAC0_DAC0") (pintype "bidirectional"))
    )
    (net (code "131") (name "unconnected-(U$1-PadDAC1)") (class "Default")
      (node (ref "U$1") (pin "DAC1") (pinfunction "DAC1_DAC1") (pintype "bidirectional"))
    )
    (net (code "132") (name "unconnected-(U$1-PadGND1)") (class "Default")
      (node (ref "U$1") (pin "GND1") (pinfunction "GND1_GND1") (pintype "bidirectional"))
    )
    (net (code "133") (name "unconnected-(U$1-PadGND_A)") (class "Default")
      (node (ref "U$1") (pin "GND_A") (pinfunction "GND_A_GND_A") (pintype "bidirectional"))
    )
    (net (code "134") (name "unconnected-(U$1-PadGND_B)") (class "Default")
      (node (ref "U$1") (pin "GND_B") (pinfunction "GND_B_GND_B") (pintype "bidirectional"))
    )
    (net (code "135") (name "unconnected-(U$1-PadGND_DEBUG)") (class "Default")
      (node (ref "U$1") (pin "GND_DEBUG") (pinfunction "GND_DEBUG_GND_DEBUG") (pintype "bidirectional"))
    )
    (net (code "136") (name "unconnected-(U$1-PadGND_ICSP)") (class "Default")
      (node (ref "U$1") (pin "GND_ICSP") (pinfunction "GND_ICSP_GND_ICSP") (pintype "bidirectional"))
    )
    (net (code "137") (name "unconnected-(U$1-PadIOREF)") (class "Default")
      (node (ref "U$1") (pin "IOREF") (pinfunction "IOREF_IOREF") (pintype "bidirectional"))
    )
    (net (code "138") (name "unconnected-(U$1-PadNC)") (class "Default")
      (node (ref "U$1") (pin "NC") (pinfunction "NC_NC") (pintype "bidirectional"))
    )
    (net (code "139") (name "unconnected-(U$1-PadRESET)") (class "Default")
      (node (ref "U$1") (pin "RESET") (pinfunction "RESET_RESET") (pintype "bidirectional"))
    )
    (net (code "140") (name "unconnected-(U$1-PadRESET_DEBUG)") (class "Default")
      (node (ref "U$1") (pin "RESET_DEBUG") (pinfunction "RESET_DEBUG_RESET_DEBUG") (pintype "bidirectional"))
    )
    (net (code "141") (name "unconnected-(U$1-PadRESET_ICSP)") (class "Default")
      (node (ref "U$1") (pin "RESET_ICSP") (pinfunction "RESET_ICSP_RESET_ICSP") (pintype "bidirectional"))
    )
    (net (code "142") (name "unconnected-(U$1-PadRX1)") (class "Default")
      (node (ref "U$1") (pin "RX1") (pinfunction "RX1_RX1") (pintype "bidirectional"))
    )
    (net (code "143") (name "unconnected-(U$1-PadSCL)") (class "Default")
      (node (ref "U$1") (pin "SCL") (pinfunction "SCL_SCL") (pintype "bidirectional"))
    )
    (net (code "144") (name "unconnected-(U$1-PadSCL1)") (class "Default")
      (node (ref "U$1") (pin "SCL1") (pinfunction "SCL1_SCL1") (pintype "bidirectional"))
    )
    (net (code "145") (name "unconnected-(U$1-PadSDA)") (class "Default")
      (node (ref "U$1") (pin "SDA") (pinfunction "SDA_SDA") (pintype "bidirectional"))
    )
    (net (code "146") (name "unconnected-(U$1-PadSDA1)") (class "Default")
      (node (ref "U$1") (pin "SDA1") (pinfunction "SDA1_SDA1") (pintype "bidirectional"))
    )
    (net (code "147") (name "unconnected-(U$1-PadSWCLK_DEBUG)") (class "Default")
      (node (ref "U$1") (pin "SWCLK_DEBUG") (pinfunction "SWCLK_DEBUG_SWCLK_DEBUG") (pintype "bidirectional"))
    )
    (net (code "148") (name "unconnected-(U$1-PadSWDIO_DEBUG)") (class "Default")
      (node (ref "U$1") (pin "SWDIO_DEBUG") (pinfunction "SWDIO_DEBUG_SWDIO_DEBUG") (pintype "bidirectional"))
    )
    (net (code "149") (name "unconnected-(U$1-PadTX1)") (class "Default")
      (node (ref "U$1") (pin "TX1") (pinfunction "TX1_TX1") (pintype "bidirectional"))
    )
    (net (code "150") (name "unconnected-(U$1-PadVIN)") (class "Default")
      (node (ref "U$1") (pin "VIN") (pinfunction "VIN_VIN") (pintype "bidirectional"))
    )
    (net (code "151") (name "unconnected-(U$5-EAOUT2-Pad6)") (class "Default")
      (node (ref "U$5") (pin "6") (pinfunction "EAOUT2_6") (pintype "bidirectional"))
    )
    (net (code "152") (name "unconnected-(U$5-NC2-Pad5)") (class "Default")
      (node (ref "U$5") (pin "5") (pinfunction "NC2_5") (pintype "bidirectional"))
    )
    (net (code "153") (name "unconnected-(U$5-REFOUT-Pad13)") (class "Default")
      (node (ref "U$5") (pin "13") (pinfunction "REFOUT_13") (pintype "bidirectional"))
    )
    (net (code "154") (name "unconnected-(U$5-REFOUT1-Pad4)") (class "Default")
      (node (ref "U$5") (pin "4") (pinfunction "REFOUT1_4") (pintype "bidirectional"))
    )
  )
)
